# Memory.net
KiCad netlist of a schematic drawn in Altium Designer
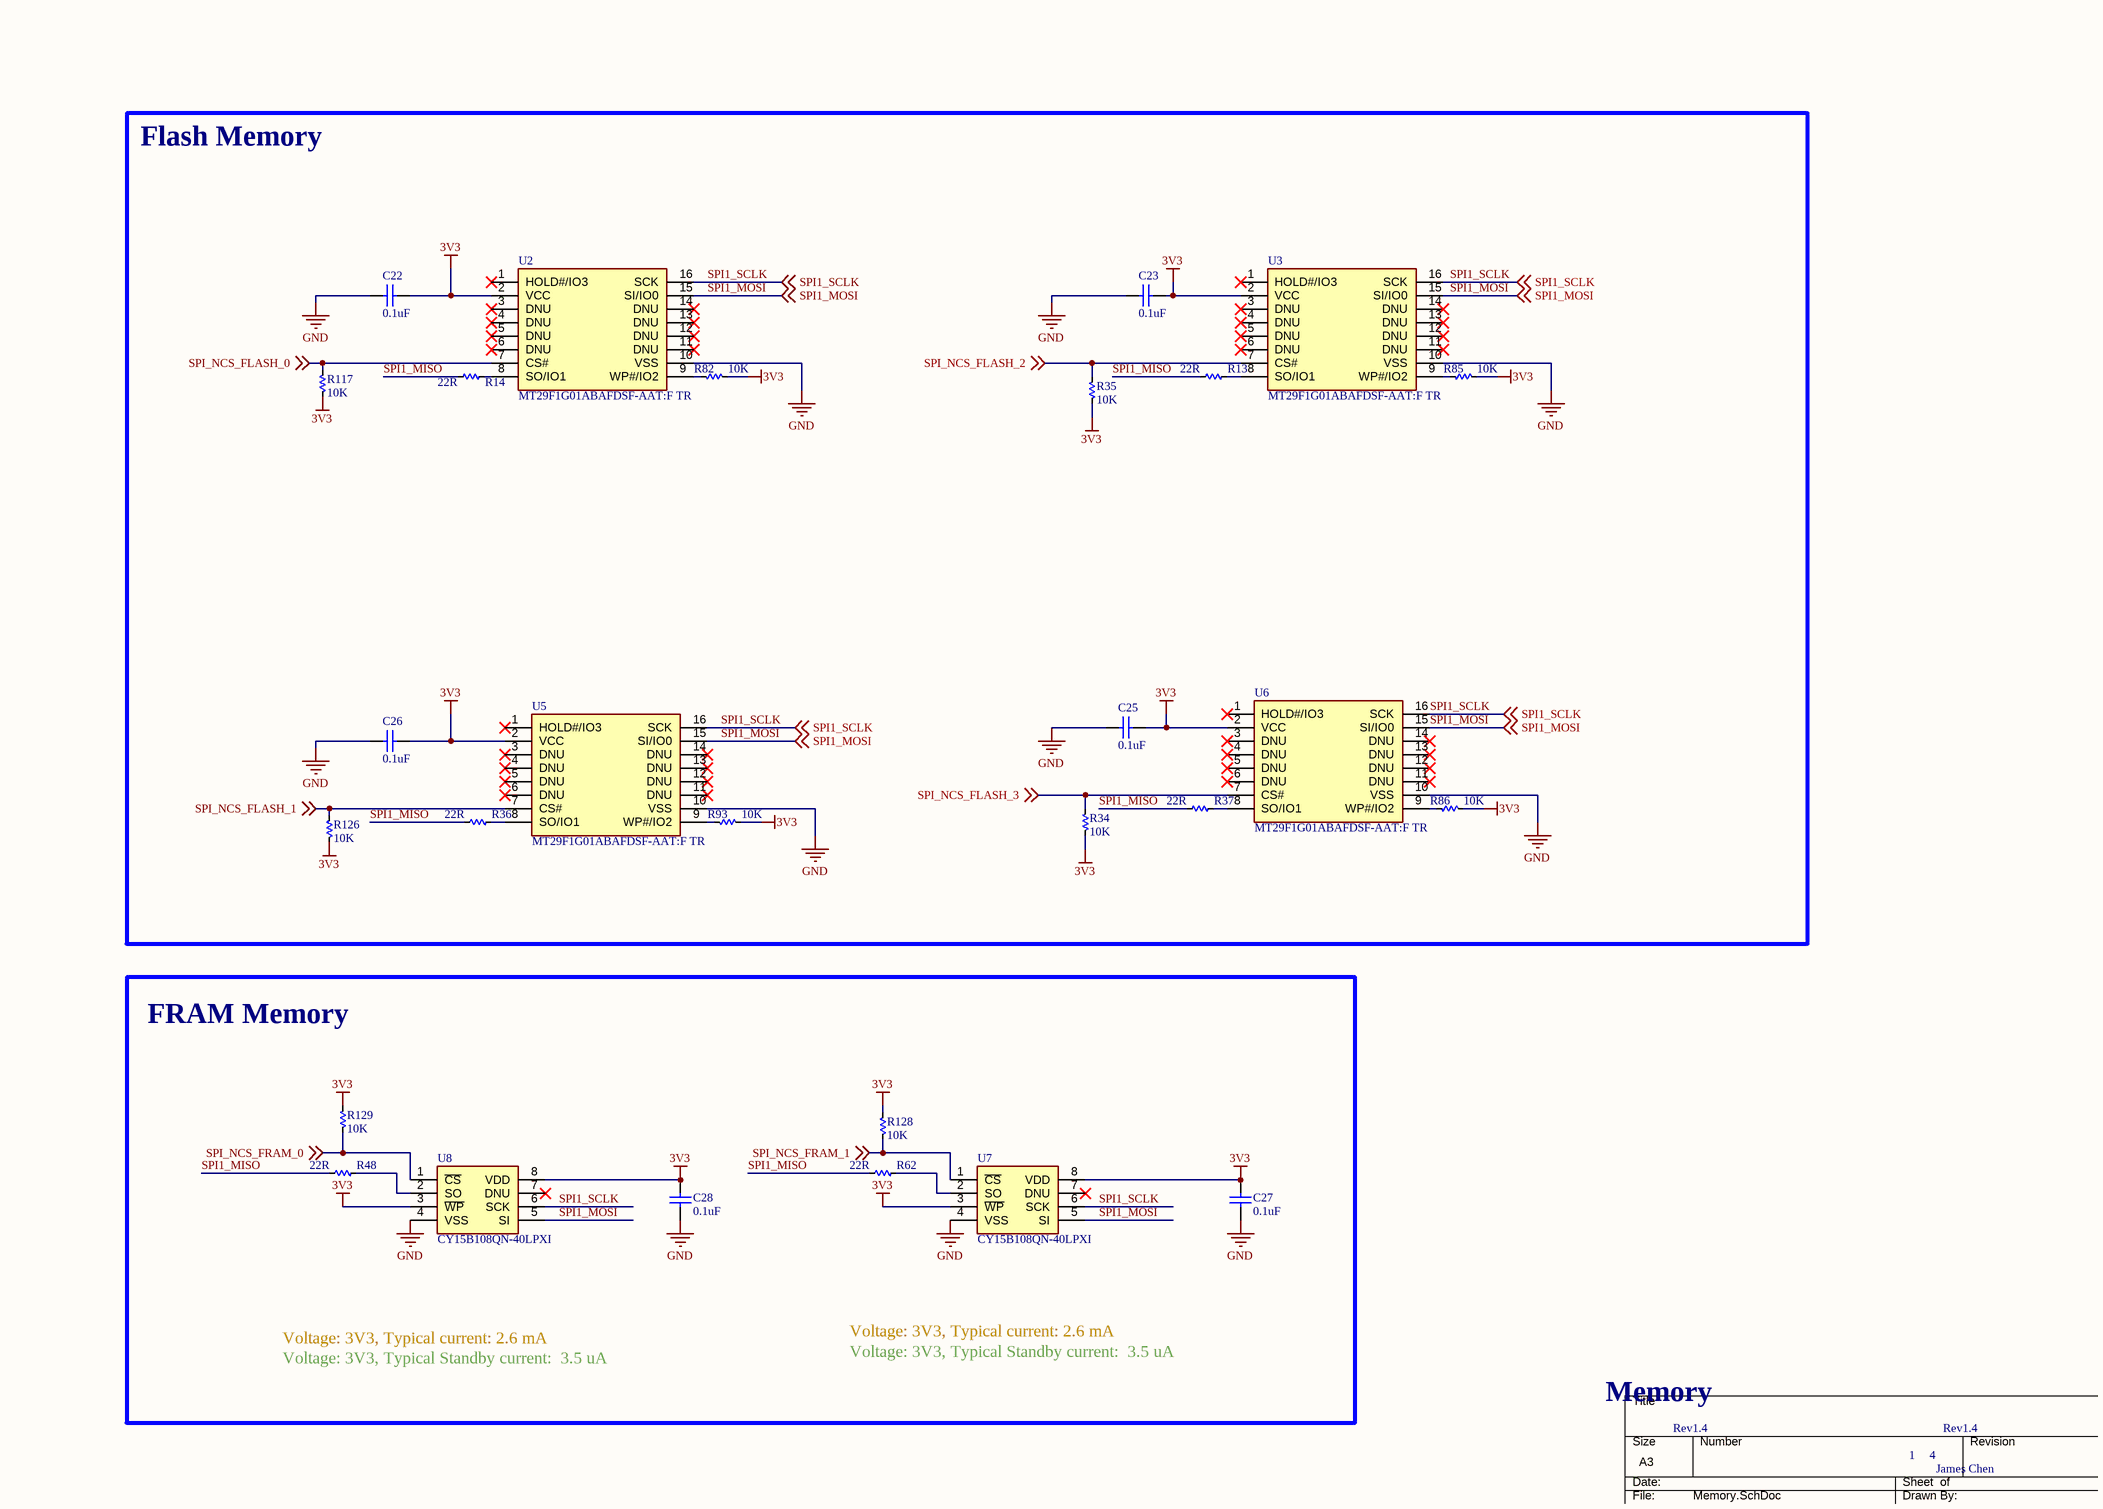
[diagram p0: Memory.SchDoc]

(export (version "E")
  (design (tool "Eeschema 10.0.6"))
  (components
    (comp (ref "C22")
      (value "0.1uF")
      (footprint "0603")
      (description "25V 100nF X7R ±10% 0603 Multilayer Ceramic Capacitors MLCC - SMD/SMT ROHS")
      (fields
        (field (name "DISTRIBUTOR PART #") "C354391")
        (field (name "MANUFACTURER") "Murata Electronics")
      )
      (libsource (lib "OBC Development Board") (part "CC-100nF-25V-X7R-0603"))
    )
    (comp (ref "C23")
      (value "0.1uF")
      (footprint "0603")
      (description "25V 100nF X7R ±10% 0603 Multilayer Ceramic Capacitors MLCC - SMD/SMT ROHS")
      (fields
        (field (name "DISTRIBUTOR PART #") "C354391")
        (field (name "MANUFACTURER") "Murata Electronics")
      )
      (libsource (lib "OBC Development Board") (part "CC-100nF-25V-X7R-0603"))
    )
    (comp (ref "C25")
      (value "0.1uF")
      (footprint "0603")
      (description "25V 100nF X7R ±10% 0603 Multilayer Ceramic Capacitors MLCC - SMD/SMT ROHS")
      (fields
        (field (name "DISTRIBUTOR PART #") "C354391")
        (field (name "MANUFACTURER") "Murata Electronics")
      )
      (libsource (lib "OBC Development Board") (part "CC-100nF-25V-X7R-0603"))
    )
    (comp (ref "C26")
      (value "0.1uF")
      (footprint "0603")
      (description "25V 100nF X7R ±10% 0603 Multilayer Ceramic Capacitors MLCC - SMD/SMT ROHS")
      (fields
        (field (name "DISTRIBUTOR PART #") "C354391")
        (field (name "MANUFACTURER") "Murata Electronics")
      )
      (libsource (lib "OBC Development Board") (part "CC-100nF-25V-X7R-0603"))
    )
    (comp (ref "C27")
      (value "0.1uF")
      (footprint "0603")
      (description "25V 100nF X7R ±10% 0603 Multilayer Ceramic Capacitors MLCC - SMD/SMT ROHS")
      (fields
        (field (name "DISTRIBUTOR PART #") "C354391")
        (field (name "MANUFACTURER") "Murata Electronics")
      )
      (libsource (lib "OBC Development Board") (part "CC-100nF-25V-X7R-0603"))
    )
    (comp (ref "C28")
      (value "0.1uF")
      (footprint "0603")
      (description "25V 100nF X7R ±10% 0603 Multilayer Ceramic Capacitors MLCC - SMD/SMT ROHS")
      (fields
        (field (name "DISTRIBUTOR PART #") "C354391")
        (field (name "MANUFACTURER") "Murata Electronics")
      )
      (libsource (lib "OBC Development Board") (part "CC-100nF-25V-X7R-0603"))
    )
    (comp (ref "R13")
      (value "22R")
      (footprint "0603")
      (description "22 Ohms ±0.5% 0.063W, 1/16W Chip Resistor 0603 (1608 Metric) - Thin Film")
      (fields (field (name "DISTRIBUTOR PART #") "RR08Q22DCT-ND") (field (name "MANUFACTURER") "Susumu"))
      (libsource (lib "OBC Development Board") (part "RT-22R0-F-1/16W-0603"))
    )
    (comp (ref "R14")
      (value "22R")
      (footprint "0603")
      (description "22 Ohms ±0.5% 0.063W, 1/16W Chip Resistor 0603 (1608 Metric) - Thin Film")
      (fields (field (name "DISTRIBUTOR PART #") "RR08Q22DCT-ND") (field (name "MANUFACTURER") "Susumu"))
      (libsource (lib "OBC Development Board") (part "RT-22R0-F-1/16W-0603"))
    )
    (comp (ref "R34")
      (value "10K")
      (footprint "0603")
      (description "10 kOhms ±0.1% 0.063W, 1/16W Chip Resistor 0603 (1608 Metric) - Thin Film")
      (fields
        (field (name "DISTRIBUTOR PART #") "A119886CT-ND")
        (field (name "MANUFACTURER") "TE Connectivity Passive Product")
      )
      (libsource (lib "OBC Development Board") (part "RT-10K0-F-1/16W-0603"))
    )
    (comp (ref "R35")
      (value "10K")
      (footprint "0603")
      (description "10 kOhms ±0.1% 0.063W, 1/16W Chip Resistor 0603 (1608 Metric) - Thin Film")
      (fields
        (field (name "DISTRIBUTOR PART #") "A119886CT-ND")
        (field (name "MANUFACTURER") "TE Connectivity Passive Product")
      )
      (libsource (lib "OBC Development Board") (part "RT-10K0-F-1/16W-0603"))
    )
    (comp (ref "R36")
      (value "22R")
      (footprint "0603")
      (description "22 Ohms ±0.5% 0.063W, 1/16W Chip Resistor 0603 (1608 Metric) - Thin Film")
      (fields (field (name "DISTRIBUTOR PART #") "RR08Q22DCT-ND") (field (name "MANUFACTURER") "Susumu"))
      (libsource (lib "OBC Development Board") (part "RT-22R0-F-1/16W-0603"))
    )
    (comp (ref "R37")
      (value "22R")
      (footprint "0603")
      (description "22 Ohms ±0.5% 0.063W, 1/16W Chip Resistor 0603 (1608 Metric) - Thin Film")
      (fields (field (name "DISTRIBUTOR PART #") "RR08Q22DCT-ND") (field (name "MANUFACTURER") "Susumu"))
      (libsource (lib "OBC Development Board") (part "RT-22R0-F-1/16W-0603"))
    )
    (comp (ref "R48")
      (value "22R")
      (footprint "0603")
      (description "22 Ohms ±0.5% 0.063W, 1/16W Chip Resistor 0603 (1608 Metric) - Thin Film")
      (fields (field (name "DISTRIBUTOR PART #") "RR08Q22DCT-ND") (field (name "MANUFACTURER") "Susumu"))
      (libsource (lib "OBC Development Board") (part "RT-22R0-F-1/16W-0603"))
    )
    (comp (ref "R62")
      (value "22R")
      (footprint "0603")
      (description "22 Ohms ±0.5% 0.063W, 1/16W Chip Resistor 0603 (1608 Metric) - Thin Film")
      (fields (field (name "DISTRIBUTOR PART #") "RR08Q22DCT-ND") (field (name "MANUFACTURER") "Susumu"))
      (libsource (lib "OBC Development Board") (part "RT-22R0-F-1/16W-0603"))
    )
    (comp (ref "R82")
      (value "10K")
      (footprint "0603")
      (description "10 kOhms ±0.1% 0.063W, 1/16W Chip Resistor 0603 (1608 Metric) - Thin Film")
      (fields
        (field (name "DISTRIBUTOR PART #") "A119886CT-ND")
        (field (name "MANUFACTURER") "TE Connectivity Passive Product")
      )
      (libsource (lib "OBC Development Board") (part "RT-10K0-F-1/16W-0603"))
    )
    (comp (ref "R85")
      (value "10K")
      (footprint "0603")
      (description "10 kOhms ±0.1% 0.063W, 1/16W Chip Resistor 0603 (1608 Metric) - Thin Film")
      (fields
        (field (name "DISTRIBUTOR PART #") "A119886CT-ND")
        (field (name "MANUFACTURER") "TE Connectivity Passive Product")
      )
      (libsource (lib "OBC Development Board") (part "RT-10K0-F-1/16W-0603"))
    )
    (comp (ref "R86")
      (value "10K")
      (footprint "0603")
      (description "10 kOhms ±0.1% 0.063W, 1/16W Chip Resistor 0603 (1608 Metric) - Thin Film")
      (fields
        (field (name "DISTRIBUTOR PART #") "A119886CT-ND")
        (field (name "MANUFACTURER") "TE Connectivity Passive Product")
      )
      (libsource (lib "OBC Development Board") (part "RT-10K0-F-1/16W-0603"))
    )
    (comp (ref "R93")
      (value "10K")
      (footprint "0603")
      (description "10 kOhms ±0.1% 0.063W, 1/16W Chip Resistor 0603 (1608 Metric) - Thin Film")
      (fields
        (field (name "DISTRIBUTOR PART #") "A119886CT-ND")
        (field (name "MANUFACTURER") "TE Connectivity Passive Product")
      )
      (libsource (lib "OBC Development Board") (part "RT-10K0-F-1/16W-0603"))
    )
    (comp (ref "R117")
      (value "10K")
      (footprint "0603")
      (description "10 kOhms ±0.1% 0.063W, 1/16W Chip Resistor 0603 (1608 Metric) - Thin Film")
      (fields
        (field (name "DISTRIBUTOR PART #") "A119886CT-ND")
        (field (name "MANUFACTURER") "TE Connectivity Passive Product")
      )
      (libsource (lib "OBC Development Board") (part "RT-10K0-F-1/16W-0603"))
    )
    (comp (ref "R126")
      (value "10K")
      (footprint "0603")
      (description "10 kOhms ±0.1% 0.063W, 1/16W Chip Resistor 0603 (1608 Metric) - Thin Film")
      (fields
        (field (name "DISTRIBUTOR PART #") "A119886CT-ND")
        (field (name "MANUFACTURER") "TE Connectivity Passive Product")
      )
      (libsource (lib "OBC Development Board") (part "RT-10K0-F-1/16W-0603"))
    )
    (comp (ref "R128")
      (value "10K")
      (footprint "0603")
      (description "10 kOhms ±0.1% 0.063W, 1/16W Chip Resistor 0603 (1608 Metric) - Thin Film")
      (fields
        (field (name "DISTRIBUTOR PART #") "A119886CT-ND")
        (field (name "MANUFACTURER") "TE Connectivity Passive Product")
      )
      (libsource (lib "OBC Development Board") (part "RT-10K0-F-1/16W-0603"))
    )
    (comp (ref "R129")
      (value "10K")
      (footprint "0603")
      (description "10 kOhms ±0.1% 0.063W, 1/16W Chip Resistor 0603 (1608 Metric) - Thin Film")
      (fields
        (field (name "DISTRIBUTOR PART #") "A119886CT-ND")
        (field (name "MANUFACTURER") "TE Connectivity Passive Product")
      )
      (libsource (lib "OBC Development Board") (part "RT-10K0-F-1/16W-0603"))
    )
    (comp (ref "U2")
      (value "MT29F1G01ABAFDSF-AAT:F TR")
      (footprint "U-MT29F1G01ABAFDSF-AAT:F TR")
      (description "IC FLASH 1GBIT SPI 16SO")
      (fields
        (field (name "MANUFACTURER") "Micron Technology Inc.")
        (field (name "DISTRIBUTER PART #") "557-1653-1-ND")
      )
      (libsource (lib "OBC Development Board") (part "U-MT29F1G01ABAFDSF-AAT{colon}F TR"))
    )
    (comp (ref "U3")
      (value "MT29F1G01ABAFDSF-AAT:F TR")
      (footprint "U-MT29F1G01ABAFDSF-AAT:F TR")
      (description "IC FLASH 1GBIT SPI 16SO")
      (fields
        (field (name "MANUFACTURER") "Micron Technology Inc.")
        (field (name "DISTRIBUTER PART #") "557-1653-1-ND")
      )
      (libsource (lib "OBC Development Board") (part "U-MT29F1G01ABAFDSF-AAT{colon}F TR"))
    )
    (comp (ref "U5")
      (value "MT29F1G01ABAFDSF-AAT:F TR")
      (footprint "U-MT29F1G01ABAFDSF-AAT:F TR")
      (description "IC FLASH 1GBIT SPI 16SO")
      (fields
        (field (name "MANUFACTURER") "Micron Technology Inc.")
        (field (name "DISTRIBUTER PART #") "557-1653-1-ND")
      )
      (libsource (lib "OBC Development Board") (part "U-MT29F1G01ABAFDSF-AAT{colon}F TR"))
    )
    (comp (ref "U6")
      (value "MT29F1G01ABAFDSF-AAT:F TR")
      (footprint "U-MT29F1G01ABAFDSF-AAT:F TR")
      (description "IC FLASH 1GBIT SPI 16SO")
      (fields
        (field (name "MANUFACTURER") "Micron Technology Inc.")
        (field (name "DISTRIBUTER PART #") "557-1653-1-ND")
      )
      (libsource (lib "OBC Development Board") (part "U-MT29F1G01ABAFDSF-AAT{colon}F TR"))
    )
    (comp (ref "U7")
      (value "CY15B108QN-40LPXI")
      (footprint "U-CY15B108QN-40LPXI")
      (description "IC FRAM 8MBIT SPI 40MHZ 8GQFN")
      (fields
        (field (name "MANUFACTURER") "Cypress Semiconductor")
        (field (name "DISTRIBUTOR PART #") "428-4723-ND")
      )
      (libsource (lib "OBC Development Board") (part "U-CY15B108QN-40LPXI"))
    )
    (comp (ref "U8")
      (value "CY15B108QN-40LPXI")
      (footprint "U-CY15B108QN-40LPXI")
      (description "IC FRAM 8MBIT SPI 40MHZ 8GQFN")
      (fields
        (field (name "MANUFACTURER") "Cypress Semiconductor")
        (field (name "DISTRIBUTOR PART #") "428-4723-ND")
      )
      (libsource (lib "OBC Development Board") (part "U-CY15B108QN-40LPXI"))
    )
  )
  (nets
    (net (code "1") (name "/SPI1_MISO") (class "Default")
      (node (ref "R13") (pin "1") (pintype "passive"))
      (node (ref "R14") (pin "1") (pintype "passive"))
      (node (ref "R36") (pin "1") (pintype "passive"))
      (node (ref "R37") (pin "1") (pintype "passive"))
      (node (ref "R48") (pin "1") (pintype "passive"))
      (node (ref "R62") (pin "1") (pintype "passive"))
    )
    (net (code "2") (name "3V3") (class "Default")
      (node (ref "C22") (pin "1") (pinfunction "1_1") (pintype "passive"))
      (node (ref "C23") (pin "2") (pinfunction "2_2") (pintype "passive"))
      (node (ref "C25") (pin "2") (pinfunction "2_2") (pintype "passive"))
      (node (ref "C26") (pin "1") (pinfunction "1_1") (pintype "passive"))
      (node (ref "C27") (pin "1") (pinfunction "1_1") (pintype "passive"))
      (node (ref "C28") (pin "1") (pinfunction "1_1") (pintype "passive"))
      (node (ref "R117") (pin "1") (pintype "passive"))
      (node (ref "R126") (pin "1") (pintype "passive"))
      (node (ref "R128") (pin "1") (pintype "passive"))
      (node (ref "R129") (pin "1") (pintype "passive"))
      (node (ref "R34") (pin "1") (pintype "passive"))
      (node (ref "R35") (pin "1") (pintype "passive"))
      (node (ref "R82") (pin "1") (pintype "passive"))
      (node (ref "R85") (pin "1") (pintype "passive"))
      (node (ref "R86") (pin "1") (pintype "passive"))
      (node (ref "R93") (pin "1") (pintype "passive"))
      (node (ref "U2") (pin "2") (pinfunction "VCC_2") (pintype "passive"))
      (node (ref "U3") (pin "2") (pinfunction "VCC_2") (pintype "passive"))
      (node (ref "U5") (pin "2") (pinfunction "VCC_2") (pintype "passive"))
      (node (ref "U6") (pin "2") (pinfunction "VCC_2") (pintype "passive"))
      (node (ref "U7") (pin "3") (pinfunction "~{WP}_3") (pintype "passive"))
      (node (ref "U7") (pin "8") (pinfunction "VDD_8") (pintype "passive"))
      (node (ref "U8") (pin "3") (pinfunction "~{WP}_3") (pintype "passive"))
      (node (ref "U8") (pin "8") (pinfunction "VDD_8") (pintype "passive"))
    )
    (net (code "3") (name "GND") (class "Default")
      (node (ref "C22") (pin "2") (pinfunction "2_2") (pintype "passive"))
      (node (ref "C23") (pin "1") (pinfunction "1_1") (pintype "passive"))
      (node (ref "C25") (pin "1") (pinfunction "1_1") (pintype "passive"))
      (node (ref "C26") (pin "2") (pinfunction "2_2") (pintype "passive"))
      (node (ref "C27") (pin "2") (pinfunction "2_2") (pintype "passive"))
      (node (ref "C28") (pin "2") (pinfunction "2_2") (pintype "passive"))
      (node (ref "U2") (pin "10") (pinfunction "VSS_10") (pintype "passive"))
      (node (ref "U3") (pin "10") (pinfunction "VSS_10") (pintype "passive"))
      (node (ref "U5") (pin "10") (pinfunction "VSS_10") (pintype "passive"))
      (node (ref "U6") (pin "10") (pinfunction "VSS_10") (pintype "passive"))
      (node (ref "U7") (pin "4") (pinfunction "VSS_4") (pintype "passive"))
      (node (ref "U8") (pin "4") (pinfunction "VSS_4") (pintype "passive"))
    )
    (net (code "4") (name "Net-(U2-SO{slash}IO1)") (class "Default")
      (node (ref "R14") (pin "2") (pintype "passive"))
      (node (ref "U2") (pin "8") (pinfunction "SO/IO1_8") (pintype "passive"))
    )
    (net (code "5") (name "Net-(U2-WP#{slash}IO2)") (class "Default")
      (node (ref "R82") (pin "2") (pintype "passive"))
      (node (ref "U2") (pin "9") (pinfunction "WP#/IO2_9") (pintype "passive"))
    )
    (net (code "6") (name "Net-(U3-SO{slash}IO1)") (class "Default")
      (node (ref "R13") (pin "2") (pintype "passive"))
      (node (ref "U3") (pin "8") (pinfunction "SO/IO1_8") (pintype "passive"))
    )
    (net (code "7") (name "Net-(U3-WP#{slash}IO2)") (class "Default")
      (node (ref "R85") (pin "2") (pintype "passive"))
      (node (ref "U3") (pin "9") (pinfunction "WP#/IO2_9") (pintype "passive"))
    )
    (net (code "8") (name "Net-(U5-SO{slash}IO1)") (class "Default")
      (node (ref "R36") (pin "2") (pintype "passive"))
      (node (ref "U5") (pin "8") (pinfunction "SO/IO1_8") (pintype "passive"))
    )
    (net (code "9") (name "Net-(U5-WP#{slash}IO2)") (class "Default")
      (node (ref "R93") (pin "2") (pintype "passive"))
      (node (ref "U5") (pin "9") (pinfunction "WP#/IO2_9") (pintype "passive"))
    )
    (net (code "10") (name "Net-(U6-SO{slash}IO1)") (class "Default")
      (node (ref "R37") (pin "2") (pintype "passive"))
      (node (ref "U6") (pin "8") (pinfunction "SO/IO1_8") (pintype "passive"))
    )
    (net (code "11") (name "Net-(U6-WP#{slash}IO2)") (class "Default")
      (node (ref "R86") (pin "2") (pintype "passive"))
      (node (ref "U6") (pin "9") (pinfunction "WP#/IO2_9") (pintype "passive"))
    )
    (net (code "12") (name "Net-(U7-SO)") (class "Default")
      (node (ref "R62") (pin "2") (pintype "passive"))
      (node (ref "U7") (pin "2") (pinfunction "SO_2") (pintype "passive"))
    )
    (net (code "13") (name "Net-(U8-SO)") (class "Default")
      (node (ref "R48") (pin "2") (pintype "passive"))
      (node (ref "U8") (pin "2") (pinfunction "SO_2") (pintype "passive"))
    )
    (net (code "14") (name "SPI1_MOSI") (class "Default")
      (node (ref "U2") (pin "15") (pinfunction "SI/IO0_15") (pintype "passive"))
      (node (ref "U3") (pin "15") (pinfunction "SI/IO0_15") (pintype "passive"))
      (node (ref "U5") (pin "15") (pinfunction "SI/IO0_15") (pintype "passive"))
      (node (ref "U6") (pin "15") (pinfunction "SI/IO0_15") (pintype "passive"))
      (node (ref "U7") (pin "5") (pinfunction "SI_5") (pintype "passive"))
      (node (ref "U8") (pin "5") (pinfunction "SI_5") (pintype "passive"))
    )
    (net (code "15") (name "SPI1_SCLK") (class "Default")
      (node (ref "U2") (pin "16") (pinfunction "SCK_16") (pintype "passive"))
      (node (ref "U3") (pin "16") (pinfunction "SCK_16") (pintype "passive"))
      (node (ref "U5") (pin "16") (pinfunction "SCK_16") (pintype "passive"))
      (node (ref "U6") (pin "16") (pinfunction "SCK_16") (pintype "passive"))
      (node (ref "U7") (pin "6") (pinfunction "SCK_6") (pintype "passive"))
      (node (ref "U8") (pin "6") (pinfunction "SCK_6") (pintype "passive"))
    )
    (net (code "16") (name "SPI_NCS_FLASH_0") (class "Default")
      (node (ref "R117") (pin "2") (pintype "passive"))
      (node (ref "U2") (pin "7") (pinfunction "CS#_7") (pintype "passive"))
    )
    (net (code "17") (name "SPI_NCS_FLASH_1") (class "Default")
      (node (ref "R126") (pin "2") (pintype "passive"))
      (node (ref "U5") (pin "7") (pinfunction "CS#_7") (pintype "passive"))
    )
    (net (code "18") (name "SPI_NCS_FLASH_2") (class "Default")
      (node (ref "R35") (pin "2") (pintype "passive"))
      (node (ref "U3") (pin "7") (pinfunction "CS#_7") (pintype "passive"))
    )
    (net (code "19") (name "SPI_NCS_FLASH_3") (class "Default")
      (node (ref "R34") (pin "2") (pintype "passive"))
      (node (ref "U6") (pin "7") (pinfunction "CS#_7") (pintype "passive"))
    )
    (net (code "20") (name "SPI_NCS_FRAM_0") (class "Default")
      (node (ref "R129") (pin "2") (pintype "passive"))
      (node (ref "U8") (pin "1") (pinfunction "~{CS}_1") (pintype "passive"))
    )
    (net (code "21") (name "SPI_NCS_FRAM_1") (class "Default")
      (node (ref "R128") (pin "2") (pintype "passive"))
      (node (ref "U7") (pin "1") (pinfunction "~{CS}_1") (pintype "passive"))
    )
    (net (code "22") (name "unconnected-(U2-DNU-Pad3)") (class "Default")
      (node (ref "U2") (pin "3") (pinfunction "DNU_3") (pintype "passive+no_connect"))
    )
    (net (code "23") (name "unconnected-(U2-DNU-Pad4)") (class "Default")
      (node (ref "U2") (pin "4") (pinfunction "DNU_4") (pintype "passive+no_connect"))
    )
    (net (code "24") (name "unconnected-(U2-DNU-Pad5)") (class "Default")
      (node (ref "U2") (pin "5") (pinfunction "DNU_5") (pintype "passive+no_connect"))
    )
    (net (code "25") (name "unconnected-(U2-DNU-Pad6)") (class "Default")
      (node (ref "U2") (pin "6") (pinfunction "DNU_6") (pintype "passive+no_connect"))
    )
    (net (code "26") (name "unconnected-(U2-DNU-Pad11)") (class "Default")
      (node (ref "U2") (pin "11") (pinfunction "DNU_11") (pintype "passive+no_connect"))
    )
    (net (code "27") (name "unconnected-(U2-DNU-Pad12)") (class "Default")
      (node (ref "U2") (pin "12") (pinfunction "DNU_12") (pintype "passive+no_connect"))
    )
    (net (code "28") (name "unconnected-(U2-DNU-Pad13)") (class "Default")
      (node (ref "U2") (pin "13") (pinfunction "DNU_13") (pintype "passive+no_connect"))
    )
    (net (code "29") (name "unconnected-(U2-DNU-Pad14)") (class "Default")
      (node (ref "U2") (pin "14") (pinfunction "DNU_14") (pintype "passive+no_connect"))
    )
    (net (code "30") (name "unconnected-(U2-HOLD#{slash}IO3-Pad1)") (class "Default")
      (node (ref "U2") (pin "1") (pinfunction "HOLD#/IO3_1") (pintype "passive+no_connect"))
    )
    (net (code "31") (name "unconnected-(U3-DNU-Pad3)") (class "Default")
      (node (ref "U3") (pin "3") (pinfunction "DNU_3") (pintype "passive+no_connect"))
    )
    (net (code "32") (name "unconnected-(U3-DNU-Pad4)") (class "Default")
      (node (ref "U3") (pin "4") (pinfunction "DNU_4") (pintype "passive+no_connect"))
    )
    (net (code "33") (name "unconnected-(U3-DNU-Pad5)") (class "Default")
      (node (ref "U3") (pin "5") (pinfunction "DNU_5") (pintype "passive+no_connect"))
    )
    (net (code "34") (name "unconnected-(U3-DNU-Pad6)") (class "Default")
      (node (ref "U3") (pin "6") (pinfunction "DNU_6") (pintype "passive+no_connect"))
    )
    (net (code "35") (name "unconnected-(U3-DNU-Pad11)") (class "Default")
      (node (ref "U3") (pin "11") (pinfunction "DNU_11") (pintype "passive+no_connect"))
    )
    (net (code "36") (name "unconnected-(U3-DNU-Pad12)") (class "Default")
      (node (ref "U3") (pin "12") (pinfunction "DNU_12") (pintype "passive+no_connect"))
    )
    (net (code "37") (name "unconnected-(U3-DNU-Pad13)") (class "Default")
      (node (ref "U3") (pin "13") (pinfunction "DNU_13") (pintype "passive+no_connect"))
    )
    (net (code "38") (name "unconnected-(U3-DNU-Pad14)") (class "Default")
      (node (ref "U3") (pin "14") (pinfunction "DNU_14") (pintype "passive+no_connect"))
    )
    (net (code "39") (name "unconnected-(U3-HOLD#{slash}IO3-Pad1)") (class "Default")
      (node (ref "U3") (pin "1") (pinfunction "HOLD#/IO3_1") (pintype "passive+no_connect"))
    )
    (net (code "40") (name "unconnected-(U5-DNU-Pad3)") (class "Default")
      (node (ref "U5") (pin "3") (pinfunction "DNU_3") (pintype "passive+no_connect"))
    )
    (net (code "41") (name "unconnected-(U5-DNU-Pad4)") (class "Default")
      (node (ref "U5") (pin "4") (pinfunction "DNU_4") (pintype "passive+no_connect"))
    )
    (net (code "42") (name "unconnected-(U5-DNU-Pad5)") (class "Default")
      (node (ref "U5") (pin "5") (pinfunction "DNU_5") (pintype "passive+no_connect"))
    )
    (net (code "43") (name "unconnected-(U5-DNU-Pad6)") (class "Default")
      (node (ref "U5") (pin "6") (pinfunction "DNU_6") (pintype "passive+no_connect"))
    )
    (net (code "44") (name "unconnected-(U5-DNU-Pad11)") (class "Default")
      (node (ref "U5") (pin "11") (pinfunction "DNU_11") (pintype "passive+no_connect"))
    )
    (net (code "45") (name "unconnected-(U5-DNU-Pad12)") (class "Default")
      (node (ref "U5") (pin "12") (pinfunction "DNU_12") (pintype "passive+no_connect"))
    )
    (net (code "46") (name "unconnected-(U5-DNU-Pad13)") (class "Default")
      (node (ref "U5") (pin "13") (pinfunction "DNU_13") (pintype "passive+no_connect"))
    )
    (net (code "47") (name "unconnected-(U5-DNU-Pad14)") (class "Default")
      (node (ref "U5") (pin "14") (pinfunction "DNU_14") (pintype "passive+no_connect"))
    )
    (net (code "48") (name "unconnected-(U5-HOLD#{slash}IO3-Pad1)") (class "Default")
      (node (ref "U5") (pin "1") (pinfunction "HOLD#/IO3_1") (pintype "passive+no_connect"))
    )
    (net (code "49") (name "unconnected-(U6-DNU-Pad3)") (class "Default")
      (node (ref "U6") (pin "3") (pinfunction "DNU_3") (pintype "passive+no_connect"))
    )
    (net (code "50") (name "unconnected-(U6-DNU-Pad4)") (class "Default")
      (node (ref "U6") (pin "4") (pinfunction "DNU_4") (pintype "passive+no_connect"))
    )
    (net (code "51") (name "unconnected-(U6-DNU-Pad5)") (class "Default")
      (node (ref "U6") (pin "5") (pinfunction "DNU_5") (pintype "passive+no_connect"))
    )
    (net (code "52") (name "unconnected-(U6-DNU-Pad6)") (class "Default")
      (node (ref "U6") (pin "6") (pinfunction "DNU_6") (pintype "passive+no_connect"))
    )
    (net (code "53") (name "unconnected-(U6-DNU-Pad11)") (class "Default")
      (node (ref "U6") (pin "11") (pinfunction "DNU_11") (pintype "passive+no_connect"))
    )
    (net (code "54") (name "unconnected-(U6-DNU-Pad12)") (class "Default")
      (node (ref "U6") (pin "12") (pinfunction "DNU_12") (pintype "passive+no_connect"))
    )
    (net (code "55") (name "unconnected-(U6-DNU-Pad13)") (class "Default")
      (node (ref "U6") (pin "13") (pinfunction "DNU_13") (pintype "passive+no_connect"))
    )
    (net (code "56") (name "unconnected-(U6-DNU-Pad14)") (class "Default")
      (node (ref "U6") (pin "14") (pinfunction "DNU_14") (pintype "passive+no_connect"))
    )
    (net (code "57") (name "unconnected-(U6-HOLD#{slash}IO3-Pad1)") (class "Default")
      (node (ref "U6") (pin "1") (pinfunction "HOLD#/IO3_1") (pintype "passive+no_connect"))
    )
    (net (code "58") (name "unconnected-(U7-DNU-Pad7)") (class "Default")
      (node (ref "U7") (pin "7") (pinfunction "DNU_7") (pintype "passive+no_connect"))
    )
    (net (code "59") (name "unconnected-(U8-DNU-Pad7)") (class "Default")
      (node (ref "U8") (pin "7") (pinfunction "DNU_7") (pintype "passive+no_connect"))
    )
  )
)
